# 15_RK3588_SARADC_1_8V_Only_GPIO.net
KiCad netlist of a schematic drawn in Altium Designer
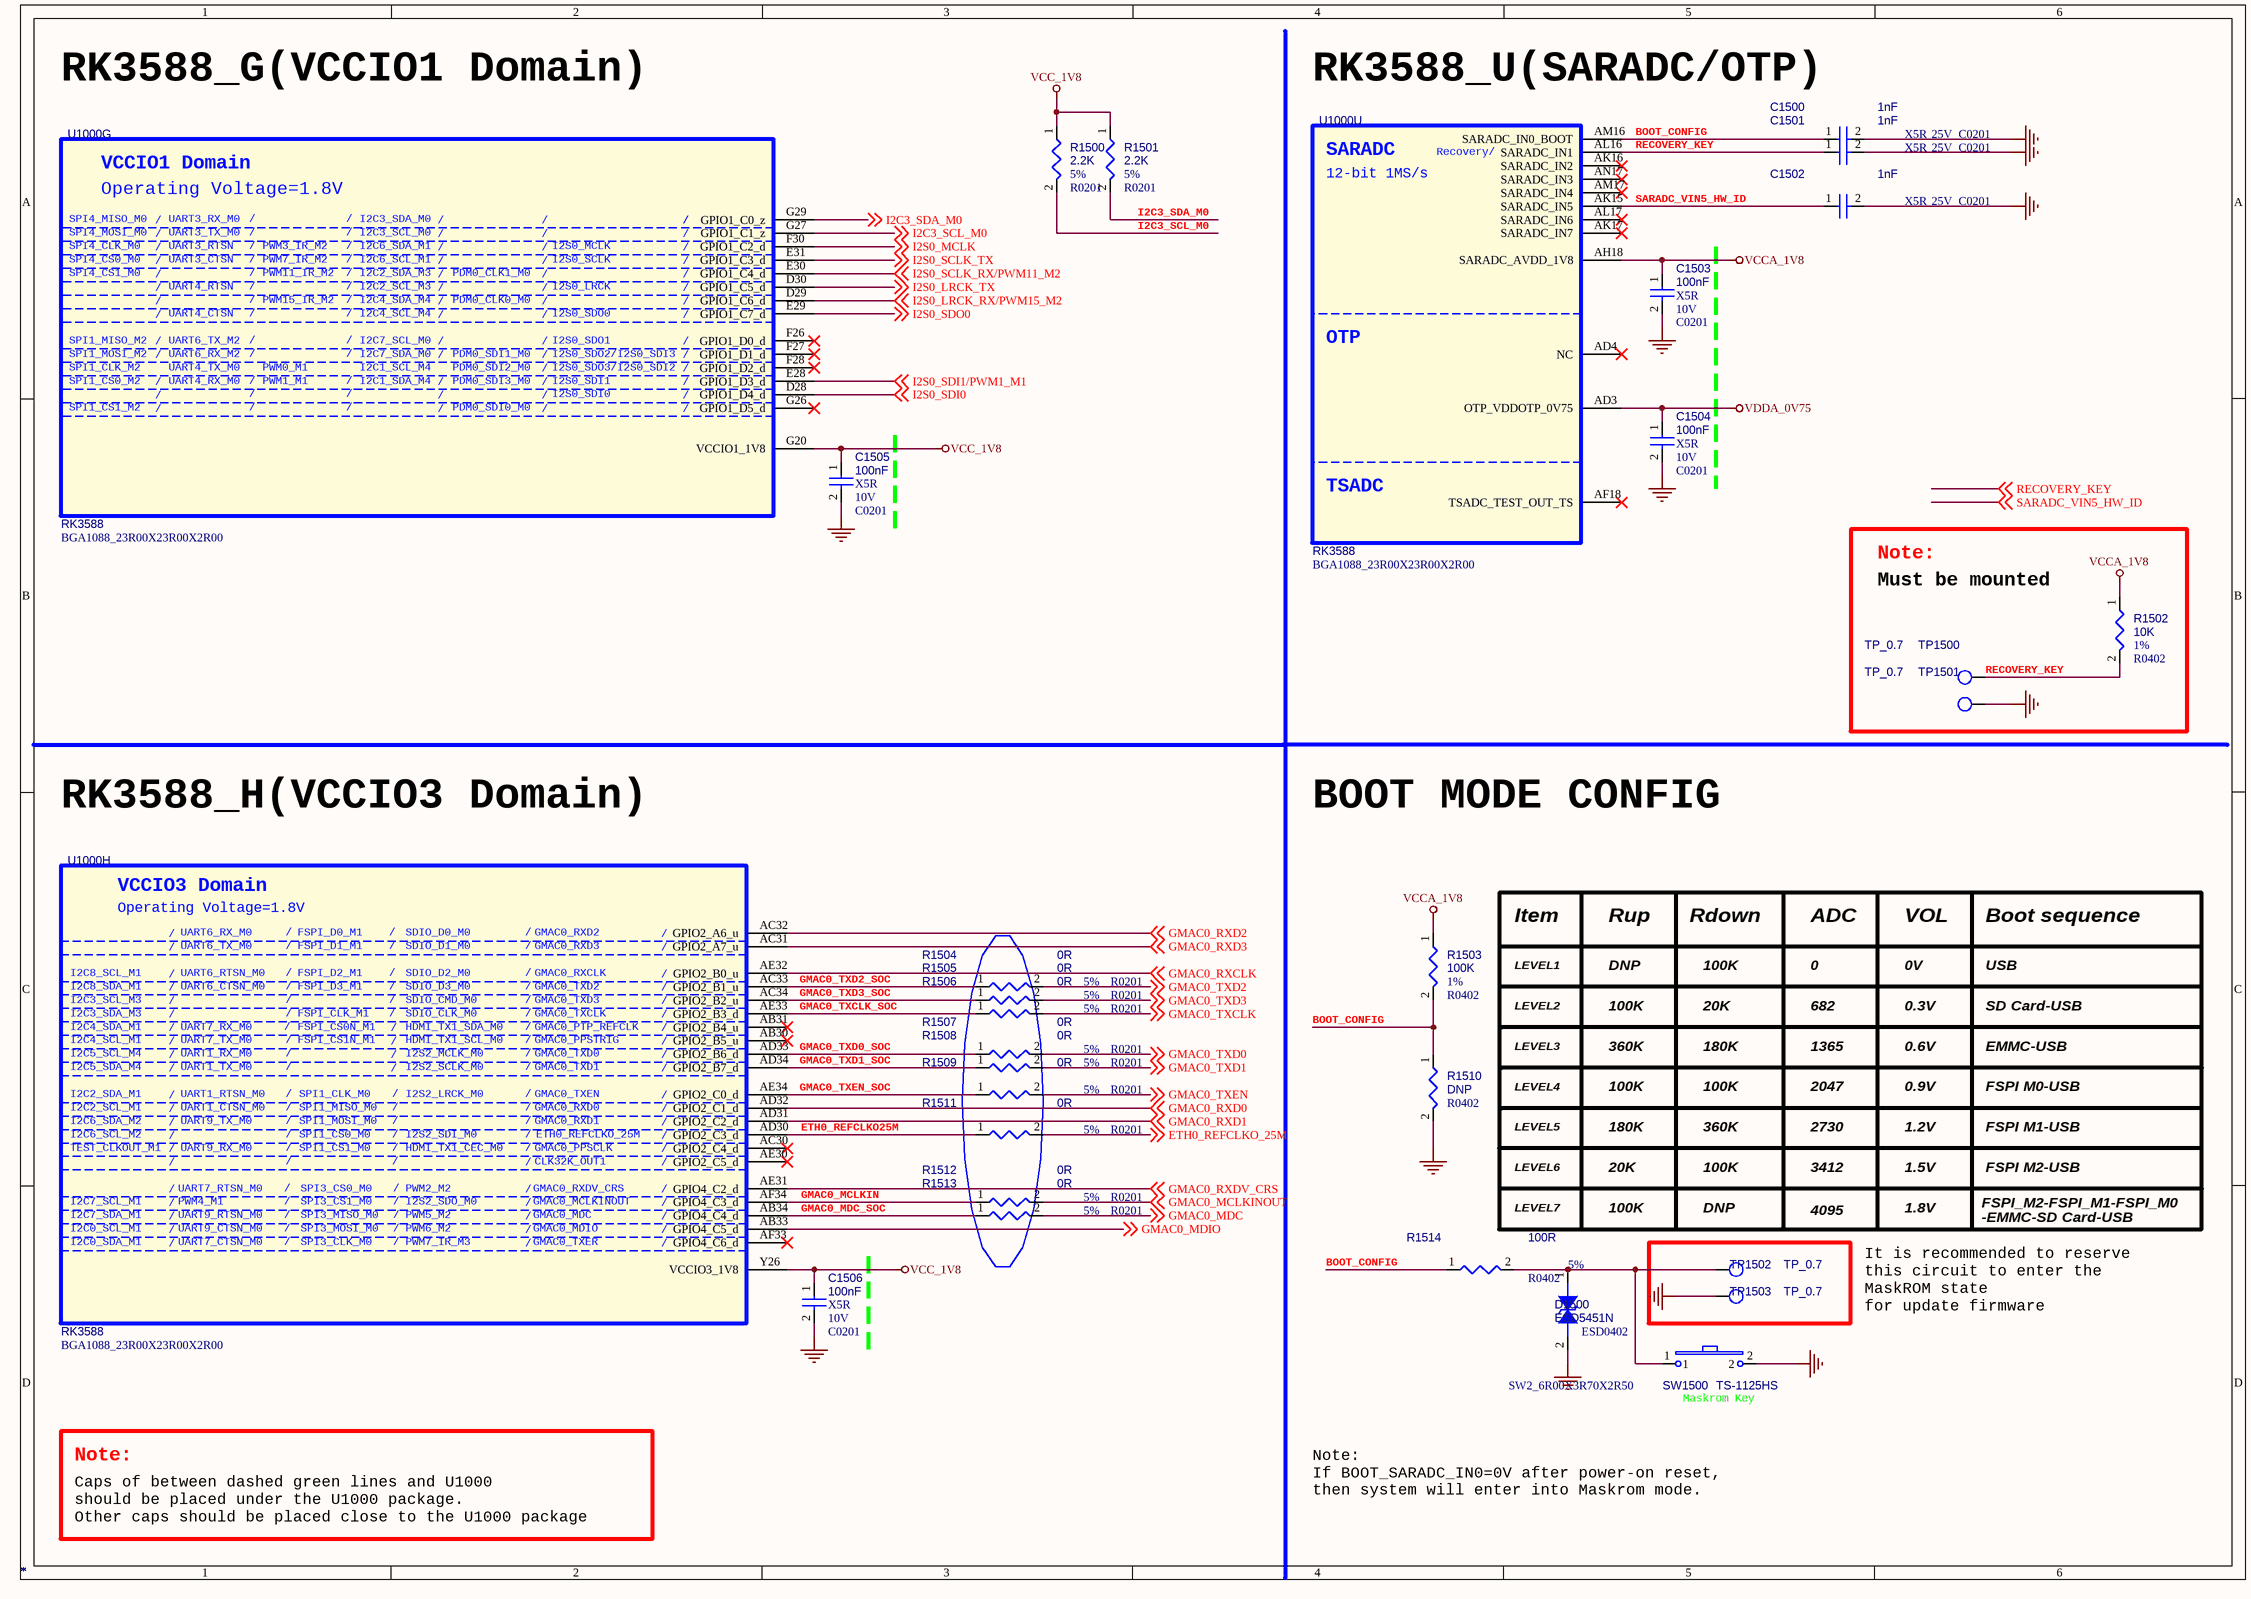
[diagram p0: 15.RK3588_SARADC_1.8V Only GPIO.SchDoc]

(export (version "E")
  (design (tool "Eeschema 10.0.6"))
  (components
    (comp (ref "C1500")
      (value "*")
      (footprint "C0201")
      (description "cap,1.00nF,+/-10%,25V,X5R,C0201")
      (fields
        (field (name "VOLTAGE") "25V")
        (field (name "PCB FOOTPRINT") "C0201")
        (field (name "DIELECTRIC") "X5R")
        (field (name "TOLERANCE") "10%")
        (field (name "MANUFACTURER") "TDK")
        (field (name "ALTIUM_UNNAMED_1") "1nF")
        (field (name "CREATED BY") "JJJ")
      )
      (libsource (lib "*") (part "CAP NP"))
    )
    (comp (ref "C1501")
      (value "*")
      (footprint "C0201")
      (description "cap,1.00nF,+/-10%,25V,X5R,C0201")
      (fields
        (field (name "VOLTAGE") "25V")
        (field (name "PCB FOOTPRINT") "C0201")
        (field (name "DIELECTRIC") "X5R")
        (field (name "TOLERANCE") "10%")
        (field (name "MANUFACTURER") "TDK")
        (field (name "ALTIUM_UNNAMED_1") "1nF")
        (field (name "CREATED BY") "JJJ")
      )
      (libsource (lib "*") (part "CAP NP"))
    )
    (comp (ref "C1502")
      (value "*")
      (footprint "C0201")
      (description "cap,1.00nF,+/-10%,25V,X5R,C0201")
      (fields
        (field (name "VOLTAGE") "25V")
        (field (name "PCB FOOTPRINT") "C0201")
        (field (name "DIELECTRIC") "X5R")
        (field (name "TOLERANCE") "10%")
        (field (name "MANUFACTURER") "TDK")
        (field (name "ALTIUM_UNNAMED_1") "1nF")
        (field (name "CREATED BY") "JJJ")
      )
      (libsource (lib "*") (part "CAP NP"))
    )
    (comp (ref "C1503")
      (value "*")
      (footprint "C0201")
      (description "cap,100.00nF,+/-10%,10V,X5R,C0201")
      (fields
        (field (name "VOLTAGE") "10V")
        (field (name "PCB FOOTPRINT") "C0201")
        (field (name "DIELECTRIC") "X5R")
        (field (name "TOLERANCE") "10%")
        (field (name "MANUFACTURER") "TDK")
        (field (name "ALTIUM_UNNAMED_1") "100nF")
        (field (name "CREATED BY") "JJJ")
      )
      (libsource (lib "*") (part "CAP NP"))
    )
    (comp (ref "C1504")
      (value "*")
      (footprint "C0201")
      (description "cap,100.00nF,+/-10%,10V,X5R,C0201")
      (fields
        (field (name "VOLTAGE") "10V")
        (field (name "PCB FOOTPRINT") "C0201")
        (field (name "DIELECTRIC") "X5R")
        (field (name "MANUFACTURER") "TDK")
        (field (name "TOLERANCE") "10%")
        (field (name "ALTIUM_UNNAMED_1") "100nF")
        (field (name "CREATED BY") "JJJ")
      )
      (libsource (lib "*") (part "CAP NP"))
    )
    (comp (ref "C1505")
      (value "*")
      (footprint "C0201")
      (description "cap,100.00nF,+/-10%,10V,X5R,C0201")
      (fields
        (field (name "VOLTAGE") "10V")
        (field (name "PCB FOOTPRINT") "C0201")
        (field (name "DIELECTRIC") "X5R")
        (field (name "MANUFACTURER") "TDK")
        (field (name "TOLERANCE") "10%")
        (field (name "ALTIUM_UNNAMED_1") "100nF")
        (field (name "CREATED BY") "JJJ")
      )
      (libsource (lib "*") (part "CAP NP"))
    )
    (comp (ref "C1506")
      (value "*")
      (footprint "C0201")
      (description "cap,100.00nF,+/-10%,10V,X5R,C0201")
      (fields
        (field (name "VOLTAGE") "10V")
        (field (name "PCB FOOTPRINT") "C0201")
        (field (name "DIELECTRIC") "X5R")
        (field (name "TOLERANCE") "10%")
        (field (name "MANUFACTURER") "TDK")
        (field (name "ALTIUM_UNNAMED_1") "100nF")
        (field (name "CREATED BY") "JJJ")
      )
      (libsource (lib "*") (part "CAP NP"))
    )
    (comp (ref "D1500")
      (value "*")
      (footprint "ESD0402")
      (description "1-Line, Bi-directional, Transient Voltage Suppressors.17.5pF.")
      (fields
        (field (name "PCB FOOTPRINT") "ESD0402")
        (field (name "MANUFACTURER") "WillSemi(О¤¶ы°лµјМе)")
        (field (name "ALTIUM_UNNAMED_1") "ESD5451N")
        (field (name "CREATED BY") "JJJ")
      )
      (libsource (lib "*") (part "DIODE BI_DIR TRIG"))
    )
    (comp (ref "R1500")
      (value "*")
      (footprint "R0402")
      (description "НЁУГєсД¤µзЧи,2K2,+/-5%,R0201,1/20W.")
      (fields
        (field (name "PCB FOOTPRINT") "R0201")
        (field (name "TOLERANCE") "5%")
        (field (name "MANUFACTURER") "YAGEO")
        (field (name "ALTIUM_UNNAMED_1") "2.2K")
        (field (name "CREATED BY") "YTL")
      )
      (libsource (lib "*") (part "RESISTOR_Dup1"))
    )
    (comp (ref "R1501")
      (value "*")
      (footprint "R0402")
      (description "НЁУГєсД¤µзЧи,2K2,+/-5%,R0201,1/20W.")
      (fields
        (field (name "PCB FOOTPRINT") "R0201")
        (field (name "TOLERANCE") "5%")
        (field (name "MANUFACTURER") "YAGEO")
        (field (name "ALTIUM_UNNAMED_1") "2.2K")
        (field (name "CREATED BY") "YTL")
      )
      (libsource (lib "*") (part "RESISTOR_Dup1"))
    )
    (comp (ref "R1502")
      (value "*")
      (footprint "R0402")
      (description "НЁУГєсД¤µзЧи,10K,+/-1%,R0402,1/16W.")
      (fields
        (field (name "PCB FOOTPRINT") "R0402")
        (field (name "TOLERANCE") "1%")
        (field (name "MANUFACTURER") "YAGEO")
        (field (name "ALTIUM_UNNAMED_1") "10K")
        (field (name "CREATED BY") "YTL")
      )
      (libsource (lib "*") (part "RESISTOR_Dup1"))
    )
    (comp (ref "R1503")
      (value "*")
      (footprint "R0402")
      (description "НЁУГєсД¤µзЧи,100K,+/-1%,R0402,1/16W.")
      (fields
        (field (name "PCB FOOTPRINT") "R0402")
        (field (name "TOLERANCE") "1%")
        (field (name "MANUFACTURER") "YAGEO")
        (field (name "ALTIUM_UNNAMED_1") "100K")
        (field (name "CREATED BY") "YTL")
      )
      (libsource (lib "*") (part "RESISTOR_Dup1"))
    )
    (comp (ref "R1504")
      (value "*")
      (footprint "R0402")
      (description "НЁУГєсД¤µзЧи,0R,+/-5%,R0201,1/20W.")
      (fields
        (field (name "PCB FOOTPRINT") "R0201")
        (field (name "TOLERANCE") "5%")
        (field (name "MANUFACTURER") "YAGEO")
        (field (name "ALTIUM_UNNAMED_1") "0R")
        (field (name "CREATED BY") "YTL")
      )
      (libsource (lib "*") (part "RESISTOR_Dup1"))
    )
    (comp (ref "R1505")
      (value "*")
      (footprint "R0402")
      (description "НЁУГєсД¤µзЧи,0R,+/-5%,R0201,1/20W.")
      (fields
        (field (name "PCB FOOTPRINT") "R0201")
        (field (name "TOLERANCE") "5%")
        (field (name "MANUFACTURER") "YAGEO")
        (field (name "ALTIUM_UNNAMED_1") "0R")
        (field (name "CREATED BY") "YTL")
      )
      (libsource (lib "*") (part "RESISTOR_Dup1"))
    )
    (comp (ref "R1506")
      (value "*")
      (footprint "R0402")
      (description "НЁУГєсД¤µзЧи,0R,+/-5%,R0201,1/20W.")
      (fields
        (field (name "PCB FOOTPRINT") "R0201")
        (field (name "TOLERANCE") "5%")
        (field (name "MANUFACTURER") "YAGEO")
        (field (name "ALTIUM_UNNAMED_1") "0R")
        (field (name "CREATED BY") "YTL")
      )
      (libsource (lib "*") (part "RESISTOR_Dup1"))
    )
    (comp (ref "R1507")
      (value "*")
      (footprint "R0402")
      (description "НЁУГєсД¤µзЧи,0R,+/-5%,R0201,1/20W.")
      (fields
        (field (name "PCB FOOTPRINT") "R0201")
        (field (name "TOLERANCE") "5%")
        (field (name "MANUFACTURER") "YAGEO")
        (field (name "ALTIUM_UNNAMED_1") "0R")
        (field (name "CREATED BY") "YTL")
      )
      (libsource (lib "*") (part "RESISTOR_Dup1"))
    )
    (comp (ref "R1508")
      (value "*")
      (footprint "R0402")
      (description "НЁУГєсД¤µзЧи,0R,+/-5%,R0201,1/20W.")
      (fields
        (field (name "PCB FOOTPRINT") "R0201")
        (field (name "TOLERANCE") "5%")
        (field (name "MANUFACTURER") "YAGEO")
        (field (name "ALTIUM_UNNAMED_1") "0R")
        (field (name "CREATED BY") "YTL")
      )
      (libsource (lib "*") (part "RESISTOR_Dup1"))
    )
    (comp (ref "R1509")
      (value "*")
      (footprint "R0402")
      (description "НЁУГєсД¤µзЧи,0R,+/-5%,R0201,1/20W.")
      (fields
        (field (name "PCB FOOTPRINT") "R0201")
        (field (name "TOLERANCE") "5%")
        (field (name "MANUFACTURER") "YAGEO")
        (field (name "ALTIUM_UNNAMED_1") "0R")
        (field (name "CREATED BY") "YTL")
      )
      (libsource (lib "*") (part "RESISTOR_Dup1"))
    )
    (comp (ref "R1510")
      (value "*")
      (footprint "R0402")
      (description "Did Not Place.")
      (fields
        (field (name "PCB FOOTPRINT") "R0402")
        (field (name "ALTIUM_UNNAMED_1") "DNP")
        (field (name "CREATED BY") "JJJ")
      )
      (libsource (lib "*") (part "RESISTOR_Dup1"))
    )
    (comp (ref "R1511")
      (value "*")
      (footprint "R0402")
      (description "НЁУГєсД¤µзЧи,0R,+/-5%,R0201,1/20W.")
      (fields
        (field (name "PCB FOOTPRINT") "R0201")
        (field (name "TOLERANCE") "5%")
        (field (name "MANUFACTURER") "YAGEO")
        (field (name "ALTIUM_UNNAMED_1") "0R")
        (field (name "CREATED BY") "YTL")
      )
      (libsource (lib "*") (part "RESISTOR_Dup1"))
    )
    (comp (ref "R1512")
      (value "*")
      (footprint "R0402")
      (description "НЁУГєсД¤µзЧи,0R,+/-5%,R0201,1/20W.")
      (fields
        (field (name "PCB FOOTPRINT") "R0201")
        (field (name "TOLERANCE") "5%")
        (field (name "MANUFACTURER") "YAGEO")
        (field (name "ALTIUM_UNNAMED_1") "0R")
        (field (name "CREATED BY") "YTL")
      )
      (libsource (lib "*") (part "RESISTOR_Dup1"))
    )
    (comp (ref "R1513")
      (value "*")
      (footprint "R0402")
      (description "НЁУГєсД¤µзЧи,0R,+/-5%,R0201,1/20W.")
      (fields
        (field (name "PCB FOOTPRINT") "R0201")
        (field (name "TOLERANCE") "5%")
        (field (name "MANUFACTURER") "YAGEO")
        (field (name "ALTIUM_UNNAMED_1") "0R")
        (field (name "CREATED BY") "YTL")
      )
      (libsource (lib "*") (part "RESISTOR_Dup1"))
    )
    (comp (ref "R1514")
      (value "*")
      (footprint "R0402")
      (description "НЁУГєсД¤µзЧи,100R,+/-5%,R0402,1/16W.")
      (fields
        (field (name "PCB FOOTPRINT") "R0402")
        (field (name "TOLERANCE") "5%")
        (field (name "MANUFACTURER") "YAGEO")
        (field (name "ALTIUM_UNNAMED_1") "100R")
        (field (name "CREATED BY") "YTL")
      )
      (libsource (lib "*") (part "RESISTOR_Dup1"))
    )
    (comp (ref "SW1500")
      (value "*")
      (footprint "YC-6615B")
      (description "2ЅЕМщЖ¬Ј¬6MMx3.7MM°ґјь")
      (fields
        (field (name "PCB FOOTPRINT") "SW2_6R00X3R70X2R50")
        (field (name "MANUFACTURER PART NUMBER") "TS-1125HS")
        (field (name "MANUFACTURER") "Сw»ЄµзЧУ")
        (field (name "OPTION") "Maskrom Key")
        (field (name "ALTIUM_UNNAMED_1") "TS-1125HS")
        (field (name "CREATED BY") "YWQ")
      )
      (libsource (lib "*") (part "KEY_2PIN"))
    )
    (comp (ref "TP1500")
      (value "*")
      (footprint "TEST")
      (description "Test Point 0.7mm")
      (fields (field (name "ALTIUM_UNNAMED_1") "TP_0.7") (field (name "CREATED BY") "JJJ"))
      (libsource (lib "*") (part "TP"))
    )
    (comp (ref "TP1501")
      (value "*")
      (footprint "TEST")
      (description "Test Point 0.7mm")
      (fields (field (name "ALTIUM_UNNAMED_1") "TP_0.7") (field (name "CREATED BY") "JJJ"))
      (libsource (lib "*") (part "TP"))
    )
    (comp (ref "TP1502")
      (value "*")
      (footprint "TEST")
      (description "Test Point 0.7mm")
      (fields (field (name "ALTIUM_UNNAMED_1") "TP_0.7") (field (name "CREATED BY") "JJJ"))
      (libsource (lib "*") (part "TP"))
    )
    (comp (ref "TP1503")
      (value "*")
      (footprint "TEST")
      (description "Test Point 0.7mm")
      (fields (field (name "ALTIUM_UNNAMED_1") "TP_0.7") (field (name "CREATED BY") "JJJ"))
      (libsource (lib "*") (part "TP"))
    )
    (comp (ref "U1000")
      (value "*")
      (footprint "BGA1088_23R00X23R00X2R00")
      (description "ROCKCHIP SOC")
      (fields
        (field (name "MANUFACTURER") "Rockchip (ИрРѕОў)")
        (field (name "PCB FOOTPRINT") "BGA1088_23R00X23R00X2R00")
        (field (name "ALTIUM_UNNAMED_1") "RK3588")
        (field (name "CREATED BY") "YWQ")
      )
      (libsource (lib "*") (part "SOC_RK3588"))
    )
  )
  (nets
    (net (code "1") (name "/BOOT_CONFIG") (class "Default")
      (node (ref "C1500") (pin "1") (pinfunction "1_1") (pintype "passive"))
      (node (ref "R1503") (pin "2") (pinfunction "2_2") (pintype "passive"))
      (node (ref "R1510") (pin "1") (pinfunction "1_1") (pintype "passive"))
      (node (ref "R1514") (pin "1") (pinfunction "1_1") (pintype "passive"))
      (node (ref "U1000") (pin "AM16") (pinfunction "SARADC_IN0_BOOT_AM16") (pintype "passive"))
    )
    (net (code "2") (name "/ETH0_REFCLKO25M") (class "Default")
      (node (ref "R1511") (pin "1") (pinfunction "1_1") (pintype "passive"))
      (node (ref "U1000") (pin "AD30") (pinfunction "GPIO2_C3_d_AD30") (pintype "passive"))
    )
    (net (code "3") (name "/GMAC0_MCLKIN") (class "Default")
      (node (ref "R1512") (pin "1") (pinfunction "1_1") (pintype "passive"))
      (node (ref "U1000") (pin "AF34") (pinfunction "GPIO4_C3_d_AF34") (pintype "passive"))
    )
    (net (code "4") (name "/GMAC0_MDC_SOC") (class "Default")
      (node (ref "R1513") (pin "1") (pinfunction "1_1") (pintype "passive"))
      (node (ref "U1000") (pin "AB34") (pinfunction "GPIO4_C4_d_AB34") (pintype "passive"))
    )
    (net (code "5") (name "/GMAC0_TXCLK_SOC") (class "Default")
      (node (ref "R1506") (pin "1") (pinfunction "1_1") (pintype "passive"))
      (node (ref "U1000") (pin "AE33") (pinfunction "GPIO2_B3_d_AE33") (pintype "passive"))
    )
    (net (code "6") (name "/GMAC0_TXD0_SOC") (class "Default")
      (node (ref "R1507") (pin "1") (pinfunction "1_1") (pintype "passive"))
      (node (ref "U1000") (pin "AD33") (pinfunction "GPIO2_B6_d_AD33") (pintype "passive"))
    )
    (net (code "7") (name "/GMAC0_TXD1_SOC") (class "Default")
      (node (ref "R1508") (pin "1") (pinfunction "1_1") (pintype "passive"))
      (node (ref "U1000") (pin "AD34") (pinfunction "GPIO2_B7_d_AD34") (pintype "passive"))
    )
    (net (code "8") (name "/GMAC0_TXD2_SOC") (class "Default")
      (node (ref "R1504") (pin "1") (pinfunction "1_1") (pintype "passive"))
      (node (ref "U1000") (pin "AC33") (pinfunction "GPIO2_B1_u_AC33") (pintype "passive"))
    )
    (net (code "9") (name "/GMAC0_TXD3_SOC") (class "Default")
      (node (ref "R1505") (pin "1") (pinfunction "1_1") (pintype "passive"))
      (node (ref "U1000") (pin "AC34") (pinfunction "GPIO2_B2_u_AC34") (pintype "passive"))
    )
    (net (code "10") (name "/GMAC0_TXEN_SOC") (class "Default")
      (node (ref "R1509") (pin "1") (pinfunction "1_1") (pintype "passive"))
      (node (ref "U1000") (pin "AE34") (pinfunction "GPIO2_C0_d_AE34") (pintype "passive"))
    )
    (net (code "11") (name "ETH0_REFCLKO_25M") (class "Default")
      (node (ref "R1511") (pin "2") (pinfunction "2_2") (pintype "passive"))
    )
    (net (code "12") (name "GMAC0_MCLKINOUT") (class "Default")
      (node (ref "R1512") (pin "2") (pinfunction "2_2") (pintype "passive"))
    )
    (net (code "13") (name "GMAC0_MDC") (class "Default")
      (node (ref "R1513") (pin "2") (pinfunction "2_2") (pintype "passive"))
    )
    (net (code "14") (name "GMAC0_MDIO") (class "Default")
      (node (ref "U1000") (pin "AB33") (pinfunction "GPIO4_C5_d_AB33") (pintype "passive"))
    )
    (net (code "15") (name "GMAC0_RXCLK") (class "Default")
      (node (ref "U1000") (pin "AE32") (pinfunction "GPIO2_B0_u_AE32") (pintype "passive"))
    )
    (net (code "16") (name "GMAC0_RXD0") (class "Default")
      (node (ref "U1000") (pin "AD32") (pinfunction "GPIO2_C1_d_AD32") (pintype "passive"))
    )
    (net (code "17") (name "GMAC0_RXD1") (class "Default")
      (node (ref "U1000") (pin "AD31") (pinfunction "GPIO2_C2_d_AD31") (pintype "passive"))
    )
    (net (code "18") (name "GMAC0_RXD2") (class "Default")
      (node (ref "U1000") (pin "AC32") (pinfunction "GPIO2_A6_u_AC32") (pintype "passive"))
    )
    (net (code "19") (name "GMAC0_RXD3") (class "Default")
      (node (ref "U1000") (pin "AC31") (pinfunction "GPIO2_A7_u_AC31") (pintype "passive"))
    )
    (net (code "20") (name "GMAC0_RXDV_CRS") (class "Default")
      (node (ref "U1000") (pin "AE31") (pinfunction "GPIO4_C2_d_AE31") (pintype "passive"))
    )
    (net (code "21") (name "GMAC0_TXCLK") (class "Default")
      (node (ref "R1506") (pin "2") (pinfunction "2_2") (pintype "passive"))
    )
    (net (code "22") (name "GMAC0_TXD0") (class "Default")
      (node (ref "R1507") (pin "2") (pinfunction "2_2") (pintype "passive"))
    )
    (net (code "23") (name "GMAC0_TXD1") (class "Default")
      (node (ref "R1508") (pin "2") (pinfunction "2_2") (pintype "passive"))
    )
    (net (code "24") (name "GMAC0_TXD2") (class "Default")
      (node (ref "R1504") (pin "2") (pinfunction "2_2") (pintype "passive"))
    )
    (net (code "25") (name "GMAC0_TXD3") (class "Default")
      (node (ref "R1505") (pin "2") (pinfunction "2_2") (pintype "passive"))
    )
    (net (code "26") (name "GMAC0_TXEN") (class "Default")
      (node (ref "R1509") (pin "2") (pinfunction "2_2") (pintype "passive"))
    )
    (net (code "27") (name "GND") (class "Default")
      (node (ref "C1500") (pin "2") (pinfunction "2_2") (pintype "passive"))
      (node (ref "C1501") (pin "2") (pinfunction "2_2") (pintype "passive"))
      (node (ref "C1502") (pin "2") (pinfunction "2_2") (pintype "passive"))
      (node (ref "C1503") (pin "2") (pinfunction "2_2") (pintype "passive"))
      (node (ref "C1504") (pin "2") (pinfunction "2_2") (pintype "passive"))
      (node (ref "C1505") (pin "2") (pinfunction "2_2") (pintype "passive"))
      (node (ref "C1506") (pin "2") (pinfunction "2_2") (pintype "passive"))
      (node (ref "D1500") (pin "2") (pinfunction "2_2") (pintype "passive"))
      (node (ref "R1510") (pin "2") (pinfunction "2_2") (pintype "passive"))
      (node (ref "SW1500") (pin "2") (pinfunction "2_2") (pintype "passive"))
      (node (ref "TP1501") (pin "1") (pinfunction "1_1") (pintype "passive"))
      (node (ref "TP1503") (pin "1") (pinfunction "1_1") (pintype "passive"))
    )
    (net (code "28") (name "I2C3_SCL_M0") (class "Default")
      (node (ref "R1500") (pin "2") (pinfunction "2_2") (pintype "passive"))
      (node (ref "U1000") (pin "G27") (pinfunction "GPIO1_C1_z_G27") (pintype "passive"))
    )
    (net (code "29") (name "I2C3_SDA_M0") (class "Default")
      (node (ref "R1501") (pin "2") (pinfunction "2_2") (pintype "passive"))
      (node (ref "U1000") (pin "G29") (pinfunction "GPIO1_C0_z_G29") (pintype "passive"))
    )
    (net (code "30") (name "I2S0_LRCK_RX{slash}PWM15_M2") (class "Default")
      (node (ref "U1000") (pin "D29") (pinfunction "GPIO1_C6_d_D29") (pintype "passive"))
    )
    (net (code "31") (name "I2S0_LRCK_TX") (class "Default")
      (node (ref "U1000") (pin "D30") (pinfunction "GPIO1_C5_d_D30") (pintype "passive"))
    )
    (net (code "32") (name "I2S0_MCLK") (class "Default")
      (node (ref "U1000") (pin "F30") (pinfunction "GPIO1_C2_d_F30") (pintype "passive"))
    )
    (net (code "33") (name "I2S0_SCLK_RX{slash}PWM11_M2") (class "Default")
      (node (ref "U1000") (pin "E30") (pinfunction "GPIO1_C4_d_E30") (pintype "passive"))
    )
    (net (code "34") (name "I2S0_SCLK_TX") (class "Default")
      (node (ref "U1000") (pin "E31") (pinfunction "GPIO1_C3_d_E31") (pintype "passive"))
    )
    (net (code "35") (name "I2S0_SDI0") (class "Default")
      (node (ref "U1000") (pin "D28") (pinfunction "GPIO1_D4_d_D28") (pintype "passive"))
    )
    (net (code "36") (name "I2S0_SDI1{slash}PWM1_M1") (class "Default")
      (node (ref "U1000") (pin "E28") (pinfunction "GPIO1_D3_d_E28") (pintype "passive"))
    )
    (net (code "37") (name "I2S0_SDO0") (class "Default")
      (node (ref "U1000") (pin "E29") (pinfunction "GPIO1_C7_d_E29") (pintype "passive"))
    )
    (net (code "38") (name "Net-(D1500-Pad1)") (class "Default")
      (node (ref "D1500") (pin "1") (pinfunction "1_1") (pintype "passive"))
      (node (ref "R1514") (pin "2") (pinfunction "2_2") (pintype "passive"))
      (node (ref "SW1500") (pin "1") (pinfunction "1_1") (pintype "passive"))
      (node (ref "TP1502") (pin "1") (pinfunction "1_1") (pintype "passive"))
    )
    (net (code "39") (name "RECOVERY_KEY") (class "Default")
      (node (ref "C1501") (pin "1") (pinfunction "1_1") (pintype "passive"))
      (node (ref "R1502") (pin "2") (pinfunction "2_2") (pintype "passive"))
      (node (ref "TP1500") (pin "1") (pinfunction "1_1") (pintype "passive"))
      (node (ref "U1000") (pin "AL16") (pinfunction "SARADC_IN1_AL16") (pintype "passive"))
    )
    (net (code "40") (name "SARADC_VIN5_HW_ID") (class "Default")
      (node (ref "C1502") (pin "1") (pinfunction "1_1") (pintype "passive"))
      (node (ref "U1000") (pin "AK15") (pinfunction "SARADC_IN5_AK15") (pintype "passive"))
    )
    (net (code "41") (name "VCCA_1V8") (class "Default")
      (node (ref "C1503") (pin "1") (pinfunction "1_1") (pintype "passive"))
      (node (ref "R1502") (pin "1") (pinfunction "1_1") (pintype "passive"))
      (node (ref "R1503") (pin "1") (pinfunction "1_1") (pintype "passive"))
      (node (ref "U1000") (pin "AH18") (pinfunction "SARADC_AVDD_1V8_AH18") (pintype "power_in"))
    )
    (net (code "42") (name "VCC_1V8") (class "Default")
      (node (ref "C1505") (pin "1") (pinfunction "1_1") (pintype "passive"))
      (node (ref "C1506") (pin "1") (pinfunction "1_1") (pintype "passive"))
      (node (ref "R1500") (pin "1") (pinfunction "1_1") (pintype "passive"))
      (node (ref "R1501") (pin "1") (pinfunction "1_1") (pintype "passive"))
      (node (ref "U1000") (pin "G20") (pinfunction "VCCIO1_1V8_G20") (pintype "passive"))
      (node (ref "U1000") (pin "Y26") (pinfunction "VCCIO3_1V8_Y26") (pintype "passive"))
    )
    (net (code "43") (name "VDDA_0V75") (class "Default")
      (node (ref "C1504") (pin "1") (pinfunction "1_1") (pintype "passive"))
      (node (ref "U1000") (pin "AD3") (pinfunction "OTP_VDDOTP_0V75_AD3") (pintype "passive"))
    )
    (net (code "44") (name "unconnected-(U1000G-GPIO1_D0_d-PadF26)") (class "Default")
      (node (ref "U1000") (pin "F26") (pinfunction "GPIO1_D0_d_F26") (pintype "passive+no_connect"))
    )
    (net (code "45") (name "unconnected-(U1000G-GPIO1_D1_d-PadF27)") (class "Default")
      (node (ref "U1000") (pin "F27") (pinfunction "GPIO1_D1_d_F27") (pintype "passive+no_connect"))
    )
    (net (code "46") (name "unconnected-(U1000G-GPIO1_D2_d-PadF28)") (class "Default")
      (node (ref "U1000") (pin "F28") (pinfunction "GPIO1_D2_d_F28") (pintype "passive+no_connect"))
    )
    (net (code "47") (name "unconnected-(U1000G-GPIO1_D5_d-PadG26)") (class "Default")
      (node (ref "U1000") (pin "G26") (pinfunction "GPIO1_D5_d_G26") (pintype "passive+no_connect"))
    )
    (net (code "48") (name "unconnected-(U1000H-GPIO2_B4_u-PadAB31)") (class "Default")
      (node (ref "U1000") (pin "AB31") (pinfunction "GPIO2_B4_u_AB31") (pintype "passive+no_connect"))
    )
    (net (code "49") (name "unconnected-(U1000H-GPIO2_B5_u-PadAB30)") (class "Default")
      (node (ref "U1000") (pin "AB30") (pinfunction "GPIO2_B5_u_AB30") (pintype "passive+no_connect"))
    )
    (net (code "50") (name "unconnected-(U1000H-GPIO2_C4_d-PadAC30)") (class "Default")
      (node (ref "U1000") (pin "AC30") (pinfunction "GPIO2_C4_d_AC30") (pintype "passive+no_connect"))
    )
    (net (code "51") (name "unconnected-(U1000H-GPIO2_C5_d-PadAE30)") (class "Default")
      (node (ref "U1000") (pin "AE30") (pinfunction "GPIO2_C5_d_AE30") (pintype "passive+no_connect"))
    )
    (net (code "52") (name "unconnected-(U1000H-GPIO4_C6_d-PadAF33)") (class "Default")
      (node (ref "U1000") (pin "AF33") (pinfunction "GPIO4_C6_d_AF33") (pintype "passive+no_connect"))
    )
    (net (code "53") (name "unconnected-(U1000U-NC-PadAD4)") (class "Default")
      (node (ref "U1000") (pin "AD4") (pinfunction "NC_AD4") (pintype "passive+no_connect"))
    )
    (net (code "54") (name "unconnected-(U1000U-SARADC_IN2-PadAK16)") (class "Default")
      (node (ref "U1000") (pin "AK16") (pinfunction "SARADC_IN2_AK16") (pintype "passive+no_connect"))
    )
    (net (code "55") (name "unconnected-(U1000U-SARADC_IN3-PadAN17)") (class "Default")
      (node (ref "U1000") (pin "AN17") (pinfunction "SARADC_IN3_AN17") (pintype "passive+no_connect"))
    )
    (net (code "56") (name "unconnected-(U1000U-SARADC_IN4-PadAM17)") (class "Default")
      (node (ref "U1000") (pin "AM17") (pinfunction "SARADC_IN4_AM17") (pintype "passive+no_connect"))
    )
    (net (code "57") (name "unconnected-(U1000U-SARADC_IN6-PadAL17)") (class "Default")
      (node (ref "U1000") (pin "AL17") (pinfunction "SARADC_IN6_AL17") (pintype "passive+no_connect"))
    )
    (net (code "58") (name "unconnected-(U1000U-SARADC_IN7-PadAK17)") (class "Default")
      (node (ref "U1000") (pin "AK17") (pinfunction "SARADC_IN7_AK17") (pintype "passive+no_connect"))
    )
    (net (code "59") (name "unconnected-(U1000U-TSADC_TEST_OUT_TS-PadAF18)") (class "Default")
      (node (ref "U1000") (pin "AF18") (pinfunction "TSADC_TEST_OUT_TS_AF18") (pintype "passive+no_connect"))
    )
  )
)
